# Connector_3.net
KiCad netlist of a schematic drawn in Altium Designer
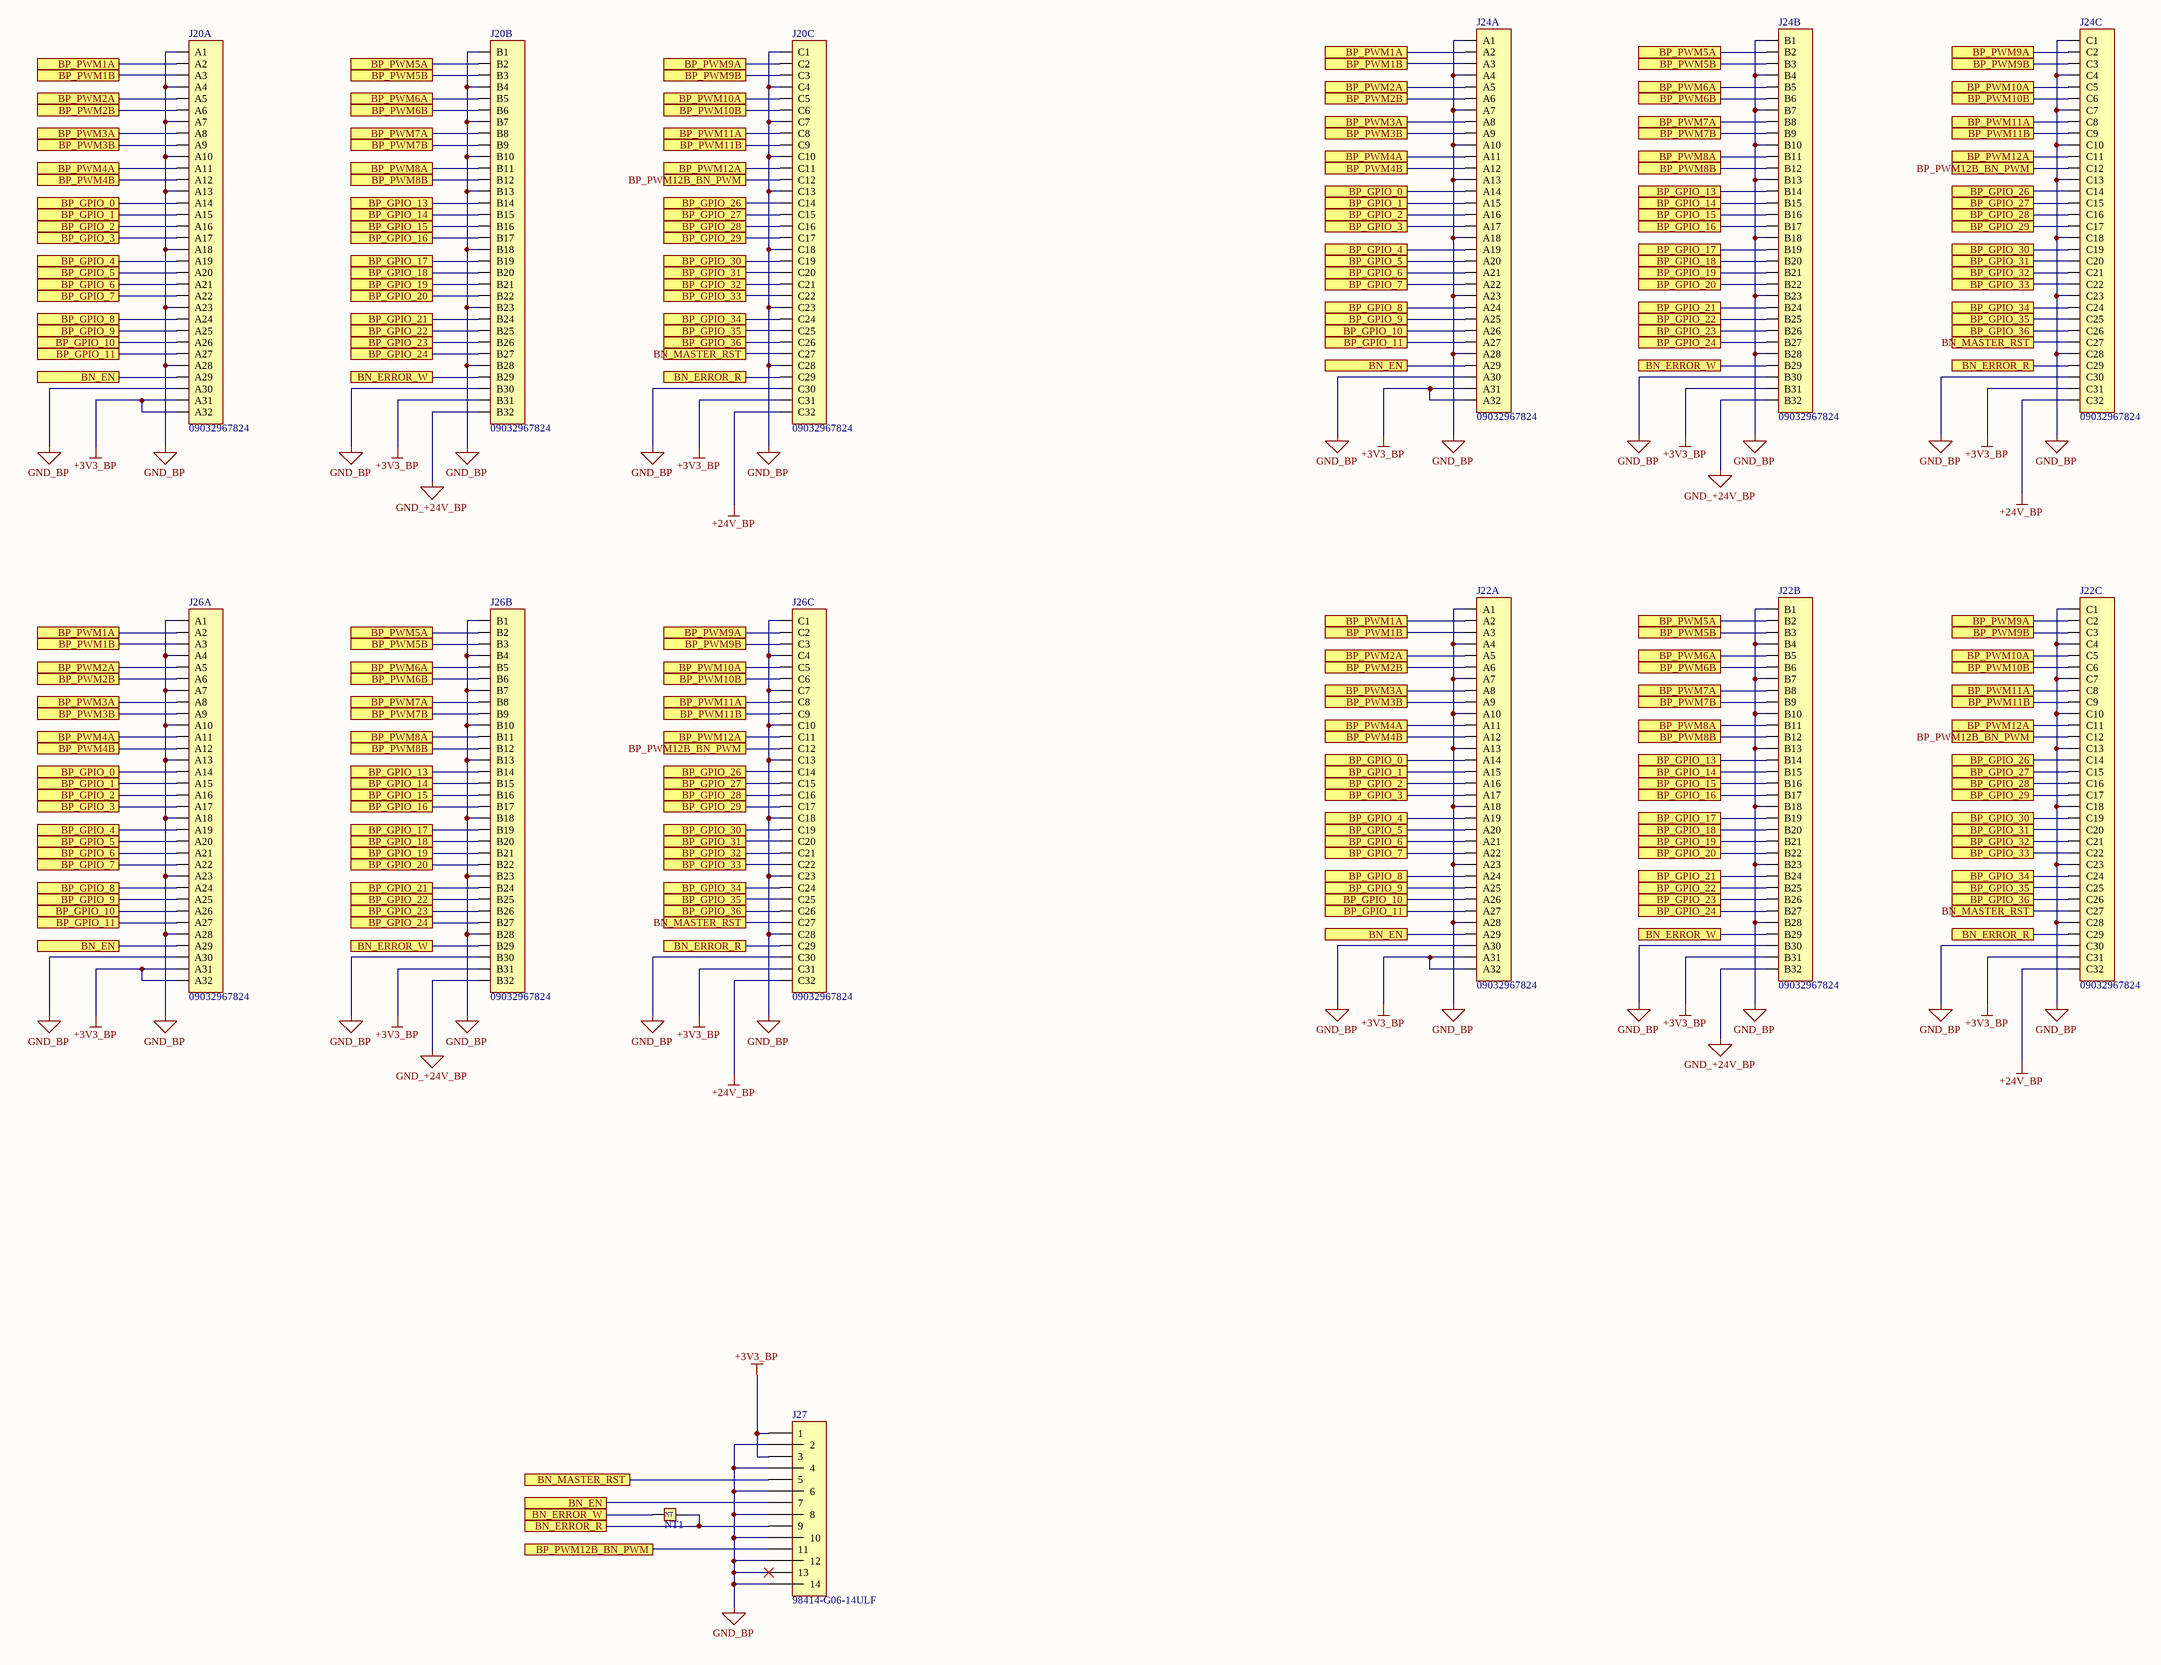
[diagram p0: Connector_3.SchDoc]

(export (version "E")
  (design (tool "Eeschema 10.0.6"))
  (components
    (comp (ref "J20")
      (value "09032967824")
      (footprint "DIN41612 FEM 3x32 ABC Straight")
      (description "DIN41612 FEM 3X32 ABC STRAIGHT")
      (fields (field (name "MANUFACTURER") "Harting"))
      (libsource (lib "Connector") (part "DIN41612 FEM 3X32 STRAIGHT"))
    )
    (comp (ref "J22")
      (value "09032967824")
      (footprint "DIN41612 FEM 3x32 ABC Straight")
      (description "DIN41612 FEM 3X32 ABC STRAIGHT")
      (fields (field (name "MANUFACTURER") "Harting"))
      (libsource (lib "Connector") (part "DIN41612 FEM 3X32 STRAIGHT"))
    )
    (comp (ref "J24")
      (value "09032967824")
      (footprint "DIN41612 FEM 3x32 ABC Straight")
      (description "DIN41612 FEM 3X32 ABC STRAIGHT")
      (fields (field (name "MANUFACTURER") "Harting"))
      (libsource (lib "Connector") (part "DIN41612 FEM 3X32 STRAIGHT"))
    )
    (comp (ref "J26")
      (value "09032967824")
      (footprint "DIN41612 FEM 3x32 ABC Straight")
      (description "DIN41612 FEM 3X32 ABC STRAIGHT")
      (fields (field (name "MANUFACTURER") "Harting"))
      (libsource (lib "Connector") (part "DIN41612 FEM 3X32 STRAIGHT"))
    )
    (comp (ref "J27")
      (value "98414-G06-14ULF")
      (footprint "FlatCable2x7 2MM Straight TH FCI 98414-G06-14ULF")
      (description "FlatCable2x7")
      (fields (field (name "MANUFACTURER") "Amphenol FCI"))
      (libsource (lib "Connector") (part "FlatCable2x7"))
    )
    (comp (ref "NT1")
      (value "Net Tie")
      (footprint "NET TIE 1005")
      (description "Connection for 2 different NETNAME")
      (libsource (lib "Jumper") (part "Net Tie"))
    )
  )
  (nets
    (net (code "1") (name "+3V3_BP") (class "Default")
      (node (ref "J20") (pin "A31") (pinfunction "A31_A31") (pintype "passive"))
      (node (ref "J20") (pin "A32") (pinfunction "A32_A32") (pintype "passive"))
      (node (ref "J20") (pin "B31") (pinfunction "B31_B31") (pintype "passive"))
      (node (ref "J20") (pin "C31") (pinfunction "C31_C31") (pintype "passive"))
      (node (ref "J22") (pin "A31") (pinfunction "A31_A31") (pintype "passive"))
      (node (ref "J22") (pin "A32") (pinfunction "A32_A32") (pintype "passive"))
      (node (ref "J22") (pin "B31") (pinfunction "B31_B31") (pintype "passive"))
      (node (ref "J22") (pin "C31") (pinfunction "C31_C31") (pintype "passive"))
      (node (ref "J24") (pin "A31") (pinfunction "A31_A31") (pintype "passive"))
      (node (ref "J24") (pin "A32") (pinfunction "A32_A32") (pintype "passive"))
      (node (ref "J24") (pin "B31") (pinfunction "B31_B31") (pintype "passive"))
      (node (ref "J24") (pin "C31") (pinfunction "C31_C31") (pintype "passive"))
      (node (ref "J26") (pin "A31") (pinfunction "A31_A31") (pintype "passive"))
      (node (ref "J26") (pin "A32") (pinfunction "A32_A32") (pintype "passive"))
      (node (ref "J26") (pin "B31") (pinfunction "B31_B31") (pintype "passive"))
      (node (ref "J26") (pin "C31") (pinfunction "C31_C31") (pintype "passive"))
      (node (ref "J27") (pin "1") (pinfunction "1_1") (pintype "passive"))
      (node (ref "J27") (pin "3") (pinfunction "3_3") (pintype "passive"))
    )
    (net (code "2") (name "+24V_BP") (class "Default")
      (node (ref "J20") (pin "C32") (pinfunction "C32_C32") (pintype "passive"))
      (node (ref "J22") (pin "C32") (pinfunction "C32_C32") (pintype "passive"))
      (node (ref "J24") (pin "C32") (pinfunction "C32_C32") (pintype "passive"))
      (node (ref "J26") (pin "C32") (pinfunction "C32_C32") (pintype "passive"))
    )
    (net (code "3") (name "/BN_EN") (class "Default")
      (node (ref "J20") (pin "A29") (pinfunction "A29_A29") (pintype "passive"))
      (node (ref "J22") (pin "A29") (pinfunction "A29_A29") (pintype "passive"))
      (node (ref "J24") (pin "A29") (pinfunction "A29_A29") (pintype "passive"))
      (node (ref "J26") (pin "A29") (pinfunction "A29_A29") (pintype "passive"))
      (node (ref "J27") (pin "7") (pinfunction "7_7") (pintype "passive"))
    )
    (net (code "4") (name "/BN_ERROR_R") (class "Default")
      (node (ref "J20") (pin "C29") (pinfunction "C29_C29") (pintype "passive"))
      (node (ref "J22") (pin "C29") (pinfunction "C29_C29") (pintype "passive"))
      (node (ref "J24") (pin "C29") (pinfunction "C29_C29") (pintype "passive"))
      (node (ref "J26") (pin "C29") (pinfunction "C29_C29") (pintype "passive"))
      (node (ref "J27") (pin "9") (pinfunction "9_9") (pintype "passive"))
      (node (ref "NT1") (pin "2") (pinfunction "2_2") (pintype "passive"))
    )
    (net (code "5") (name "/BN_ERROR_W") (class "Default")
      (node (ref "J20") (pin "B29") (pinfunction "B29_B29") (pintype "passive"))
      (node (ref "J22") (pin "B29") (pinfunction "B29_B29") (pintype "passive"))
      (node (ref "J24") (pin "B29") (pinfunction "B29_B29") (pintype "passive"))
      (node (ref "J26") (pin "B29") (pinfunction "B29_B29") (pintype "passive"))
      (node (ref "NT1") (pin "1") (pinfunction "1_1") (pintype "passive"))
    )
    (net (code "6") (name "/BN_MASTER_RST") (class "Default")
      (node (ref "J20") (pin "C27") (pinfunction "C27_C27") (pintype "passive"))
      (node (ref "J22") (pin "C27") (pinfunction "C27_C27") (pintype "passive"))
      (node (ref "J24") (pin "C27") (pinfunction "C27_C27") (pintype "passive"))
      (node (ref "J26") (pin "C27") (pinfunction "C27_C27") (pintype "passive"))
      (node (ref "J27") (pin "5") (pinfunction "5_5") (pintype "passive"))
    )
    (net (code "7") (name "/BP_GPIO_0") (class "Default")
      (node (ref "J20") (pin "A14") (pinfunction "A14_A14") (pintype "passive"))
      (node (ref "J22") (pin "A14") (pinfunction "A14_A14") (pintype "passive"))
      (node (ref "J24") (pin "A14") (pinfunction "A14_A14") (pintype "passive"))
      (node (ref "J26") (pin "A14") (pinfunction "A14_A14") (pintype "passive"))
    )
    (net (code "8") (name "/BP_GPIO_1") (class "Default")
      (node (ref "J20") (pin "A15") (pinfunction "A15_A15") (pintype "passive"))
      (node (ref "J22") (pin "A15") (pinfunction "A15_A15") (pintype "passive"))
      (node (ref "J24") (pin "A15") (pinfunction "A15_A15") (pintype "passive"))
      (node (ref "J26") (pin "A15") (pinfunction "A15_A15") (pintype "passive"))
    )
    (net (code "9") (name "/BP_GPIO_2") (class "Default")
      (node (ref "J20") (pin "A16") (pinfunction "A16_A16") (pintype "passive"))
      (node (ref "J22") (pin "A16") (pinfunction "A16_A16") (pintype "passive"))
      (node (ref "J24") (pin "A16") (pinfunction "A16_A16") (pintype "passive"))
      (node (ref "J26") (pin "A16") (pinfunction "A16_A16") (pintype "passive"))
    )
    (net (code "10") (name "/BP_GPIO_3") (class "Default")
      (node (ref "J20") (pin "A17") (pinfunction "A17_A17") (pintype "passive"))
      (node (ref "J22") (pin "A17") (pinfunction "A17_A17") (pintype "passive"))
      (node (ref "J24") (pin "A17") (pinfunction "A17_A17") (pintype "passive"))
      (node (ref "J26") (pin "A17") (pinfunction "A17_A17") (pintype "passive"))
    )
    (net (code "11") (name "/BP_GPIO_4") (class "Default")
      (node (ref "J20") (pin "A19") (pinfunction "A19_A19") (pintype "passive"))
      (node (ref "J22") (pin "A19") (pinfunction "A19_A19") (pintype "passive"))
      (node (ref "J24") (pin "A19") (pinfunction "A19_A19") (pintype "passive"))
      (node (ref "J26") (pin "A19") (pinfunction "A19_A19") (pintype "passive"))
    )
    (net (code "12") (name "/BP_GPIO_5") (class "Default")
      (node (ref "J20") (pin "A20") (pinfunction "A20_A20") (pintype "passive"))
      (node (ref "J22") (pin "A20") (pinfunction "A20_A20") (pintype "passive"))
      (node (ref "J24") (pin "A20") (pinfunction "A20_A20") (pintype "passive"))
      (node (ref "J26") (pin "A20") (pinfunction "A20_A20") (pintype "passive"))
    )
    (net (code "13") (name "/BP_GPIO_6") (class "Default")
      (node (ref "J20") (pin "A21") (pinfunction "A21_A21") (pintype "passive"))
      (node (ref "J22") (pin "A21") (pinfunction "A21_A21") (pintype "passive"))
      (node (ref "J24") (pin "A21") (pinfunction "A21_A21") (pintype "passive"))
      (node (ref "J26") (pin "A21") (pinfunction "A21_A21") (pintype "passive"))
    )
    (net (code "14") (name "/BP_GPIO_7") (class "Default")
      (node (ref "J20") (pin "A22") (pinfunction "A22_A22") (pintype "passive"))
      (node (ref "J22") (pin "A22") (pinfunction "A22_A22") (pintype "passive"))
      (node (ref "J24") (pin "A22") (pinfunction "A22_A22") (pintype "passive"))
      (node (ref "J26") (pin "A22") (pinfunction "A22_A22") (pintype "passive"))
    )
    (net (code "15") (name "/BP_GPIO_8") (class "Default")
      (node (ref "J20") (pin "A24") (pinfunction "A24_A24") (pintype "passive"))
      (node (ref "J22") (pin "A24") (pinfunction "A24_A24") (pintype "passive"))
      (node (ref "J24") (pin "A24") (pinfunction "A24_A24") (pintype "passive"))
      (node (ref "J26") (pin "A24") (pinfunction "A24_A24") (pintype "passive"))
    )
    (net (code "16") (name "/BP_GPIO_9") (class "Default")
      (node (ref "J20") (pin "A25") (pinfunction "A25_A25") (pintype "passive"))
      (node (ref "J22") (pin "A25") (pinfunction "A25_A25") (pintype "passive"))
      (node (ref "J24") (pin "A25") (pinfunction "A25_A25") (pintype "passive"))
      (node (ref "J26") (pin "A25") (pinfunction "A25_A25") (pintype "passive"))
    )
    (net (code "17") (name "/BP_GPIO_10") (class "Default")
      (node (ref "J20") (pin "A26") (pinfunction "A26_A26") (pintype "passive"))
      (node (ref "J22") (pin "A26") (pinfunction "A26_A26") (pintype "passive"))
      (node (ref "J24") (pin "A26") (pinfunction "A26_A26") (pintype "passive"))
      (node (ref "J26") (pin "A26") (pinfunction "A26_A26") (pintype "passive"))
    )
    (net (code "18") (name "/BP_GPIO_11") (class "Default")
      (node (ref "J20") (pin "A27") (pinfunction "A27_A27") (pintype "passive"))
      (node (ref "J22") (pin "A27") (pinfunction "A27_A27") (pintype "passive"))
      (node (ref "J24") (pin "A27") (pinfunction "A27_A27") (pintype "passive"))
      (node (ref "J26") (pin "A27") (pinfunction "A27_A27") (pintype "passive"))
    )
    (net (code "19") (name "/BP_GPIO_13") (class "Default")
      (node (ref "J20") (pin "B14") (pinfunction "B14_B14") (pintype "passive"))
      (node (ref "J22") (pin "B14") (pinfunction "B14_B14") (pintype "passive"))
      (node (ref "J24") (pin "B14") (pinfunction "B14_B14") (pintype "passive"))
      (node (ref "J26") (pin "B14") (pinfunction "B14_B14") (pintype "passive"))
    )
    (net (code "20") (name "/BP_GPIO_14") (class "Default")
      (node (ref "J20") (pin "B15") (pinfunction "B15_B15") (pintype "passive"))
      (node (ref "J22") (pin "B15") (pinfunction "B15_B15") (pintype "passive"))
      (node (ref "J24") (pin "B15") (pinfunction "B15_B15") (pintype "passive"))
      (node (ref "J26") (pin "B15") (pinfunction "B15_B15") (pintype "passive"))
    )
    (net (code "21") (name "/BP_GPIO_15") (class "Default")
      (node (ref "J20") (pin "B16") (pinfunction "B16_B16") (pintype "passive"))
      (node (ref "J22") (pin "B16") (pinfunction "B16_B16") (pintype "passive"))
      (node (ref "J24") (pin "B16") (pinfunction "B16_B16") (pintype "passive"))
      (node (ref "J26") (pin "B16") (pinfunction "B16_B16") (pintype "passive"))
    )
    (net (code "22") (name "/BP_GPIO_16") (class "Default")
      (node (ref "J20") (pin "B17") (pinfunction "B17_B17") (pintype "passive"))
      (node (ref "J22") (pin "B17") (pinfunction "B17_B17") (pintype "passive"))
      (node (ref "J24") (pin "B17") (pinfunction "B17_B17") (pintype "passive"))
      (node (ref "J26") (pin "B17") (pinfunction "B17_B17") (pintype "passive"))
    )
    (net (code "23") (name "/BP_GPIO_17") (class "Default")
      (node (ref "J20") (pin "B19") (pinfunction "B19_B19") (pintype "passive"))
      (node (ref "J22") (pin "B19") (pinfunction "B19_B19") (pintype "passive"))
      (node (ref "J24") (pin "B19") (pinfunction "B19_B19") (pintype "passive"))
      (node (ref "J26") (pin "B19") (pinfunction "B19_B19") (pintype "passive"))
    )
    (net (code "24") (name "/BP_GPIO_18") (class "Default")
      (node (ref "J20") (pin "B20") (pinfunction "B20_B20") (pintype "passive"))
      (node (ref "J22") (pin "B20") (pinfunction "B20_B20") (pintype "passive"))
      (node (ref "J24") (pin "B20") (pinfunction "B20_B20") (pintype "passive"))
      (node (ref "J26") (pin "B20") (pinfunction "B20_B20") (pintype "passive"))
    )
    (net (code "25") (name "/BP_GPIO_19") (class "Default")
      (node (ref "J20") (pin "B21") (pinfunction "B21_B21") (pintype "passive"))
      (node (ref "J22") (pin "B21") (pinfunction "B21_B21") (pintype "passive"))
      (node (ref "J24") (pin "B21") (pinfunction "B21_B21") (pintype "passive"))
      (node (ref "J26") (pin "B21") (pinfunction "B21_B21") (pintype "passive"))
    )
    (net (code "26") (name "/BP_GPIO_20") (class "Default")
      (node (ref "J20") (pin "B22") (pinfunction "B22_B22") (pintype "passive"))
      (node (ref "J22") (pin "B22") (pinfunction "B22_B22") (pintype "passive"))
      (node (ref "J24") (pin "B22") (pinfunction "B22_B22") (pintype "passive"))
      (node (ref "J26") (pin "B22") (pinfunction "B22_B22") (pintype "passive"))
    )
    (net (code "27") (name "/BP_GPIO_21") (class "Default")
      (node (ref "J20") (pin "B24") (pinfunction "B24_B24") (pintype "passive"))
      (node (ref "J22") (pin "B24") (pinfunction "B24_B24") (pintype "passive"))
      (node (ref "J24") (pin "B24") (pinfunction "B24_B24") (pintype "passive"))
      (node (ref "J26") (pin "B24") (pinfunction "B24_B24") (pintype "passive"))
    )
    (net (code "28") (name "/BP_GPIO_22") (class "Default")
      (node (ref "J20") (pin "B25") (pinfunction "B25_B25") (pintype "passive"))
      (node (ref "J22") (pin "B25") (pinfunction "B25_B25") (pintype "passive"))
      (node (ref "J24") (pin "B25") (pinfunction "B25_B25") (pintype "passive"))
      (node (ref "J26") (pin "B25") (pinfunction "B25_B25") (pintype "passive"))
    )
    (net (code "29") (name "/BP_GPIO_23") (class "Default")
      (node (ref "J20") (pin "B26") (pinfunction "B26_B26") (pintype "passive"))
      (node (ref "J22") (pin "B26") (pinfunction "B26_B26") (pintype "passive"))
      (node (ref "J24") (pin "B26") (pinfunction "B26_B26") (pintype "passive"))
      (node (ref "J26") (pin "B26") (pinfunction "B26_B26") (pintype "passive"))
    )
    (net (code "30") (name "/BP_GPIO_24") (class "Default")
      (node (ref "J20") (pin "B27") (pinfunction "B27_B27") (pintype "passive"))
      (node (ref "J22") (pin "B27") (pinfunction "B27_B27") (pintype "passive"))
      (node (ref "J24") (pin "B27") (pinfunction "B27_B27") (pintype "passive"))
      (node (ref "J26") (pin "B27") (pinfunction "B27_B27") (pintype "passive"))
    )
    (net (code "31") (name "/BP_GPIO_26") (class "Default")
      (node (ref "J20") (pin "C14") (pinfunction "C14_C14") (pintype "passive"))
      (node (ref "J22") (pin "C14") (pinfunction "C14_C14") (pintype "passive"))
      (node (ref "J24") (pin "C14") (pinfunction "C14_C14") (pintype "passive"))
      (node (ref "J26") (pin "C14") (pinfunction "C14_C14") (pintype "passive"))
    )
    (net (code "32") (name "/BP_GPIO_27") (class "Default")
      (node (ref "J20") (pin "C15") (pinfunction "C15_C15") (pintype "passive"))
      (node (ref "J22") (pin "C15") (pinfunction "C15_C15") (pintype "passive"))
      (node (ref "J24") (pin "C15") (pinfunction "C15_C15") (pintype "passive"))
      (node (ref "J26") (pin "C15") (pinfunction "C15_C15") (pintype "passive"))
    )
    (net (code "33") (name "/BP_GPIO_28") (class "Default")
      (node (ref "J20") (pin "C16") (pinfunction "C16_C16") (pintype "passive"))
      (node (ref "J22") (pin "C16") (pinfunction "C16_C16") (pintype "passive"))
      (node (ref "J24") (pin "C16") (pinfunction "C16_C16") (pintype "passive"))
      (node (ref "J26") (pin "C16") (pinfunction "C16_C16") (pintype "passive"))
    )
    (net (code "34") (name "/BP_GPIO_29") (class "Default")
      (node (ref "J20") (pin "C17") (pinfunction "C17_C17") (pintype "passive"))
      (node (ref "J22") (pin "C17") (pinfunction "C17_C17") (pintype "passive"))
      (node (ref "J24") (pin "C17") (pinfunction "C17_C17") (pintype "passive"))
      (node (ref "J26") (pin "C17") (pinfunction "C17_C17") (pintype "passive"))
    )
    (net (code "35") (name "/BP_GPIO_30") (class "Default")
      (node (ref "J20") (pin "C19") (pinfunction "C19_C19") (pintype "passive"))
      (node (ref "J22") (pin "C19") (pinfunction "C19_C19") (pintype "passive"))
      (node (ref "J24") (pin "C19") (pinfunction "C19_C19") (pintype "passive"))
      (node (ref "J26") (pin "C19") (pinfunction "C19_C19") (pintype "passive"))
    )
    (net (code "36") (name "/BP_GPIO_31") (class "Default")
      (node (ref "J20") (pin "C20") (pinfunction "C20_C20") (pintype "passive"))
      (node (ref "J22") (pin "C20") (pinfunction "C20_C20") (pintype "passive"))
      (node (ref "J24") (pin "C20") (pinfunction "C20_C20") (pintype "passive"))
      (node (ref "J26") (pin "C20") (pinfunction "C20_C20") (pintype "passive"))
    )
    (net (code "37") (name "/BP_GPIO_32") (class "Default")
      (node (ref "J20") (pin "C21") (pinfunction "C21_C21") (pintype "passive"))
      (node (ref "J22") (pin "C21") (pinfunction "C21_C21") (pintype "passive"))
      (node (ref "J24") (pin "C21") (pinfunction "C21_C21") (pintype "passive"))
      (node (ref "J26") (pin "C21") (pinfunction "C21_C21") (pintype "passive"))
    )
    (net (code "38") (name "/BP_GPIO_33") (class "Default")
      (node (ref "J20") (pin "C22") (pinfunction "C22_C22") (pintype "passive"))
      (node (ref "J22") (pin "C22") (pinfunction "C22_C22") (pintype "passive"))
      (node (ref "J24") (pin "C22") (pinfunction "C22_C22") (pintype "passive"))
      (node (ref "J26") (pin "C22") (pinfunction "C22_C22") (pintype "passive"))
    )
    (net (code "39") (name "/BP_GPIO_34") (class "Default")
      (node (ref "J20") (pin "C24") (pinfunction "C24_C24") (pintype "passive"))
      (node (ref "J22") (pin "C24") (pinfunction "C24_C24") (pintype "passive"))
      (node (ref "J24") (pin "C24") (pinfunction "C24_C24") (pintype "passive"))
      (node (ref "J26") (pin "C24") (pinfunction "C24_C24") (pintype "passive"))
    )
    (net (code "40") (name "/BP_GPIO_35") (class "Default")
      (node (ref "J20") (pin "C25") (pinfunction "C25_C25") (pintype "passive"))
      (node (ref "J22") (pin "C25") (pinfunction "C25_C25") (pintype "passive"))
      (node (ref "J24") (pin "C25") (pinfunction "C25_C25") (pintype "passive"))
      (node (ref "J26") (pin "C25") (pinfunction "C25_C25") (pintype "passive"))
    )
    (net (code "41") (name "/BP_GPIO_36") (class "Default")
      (node (ref "J20") (pin "C26") (pinfunction "C26_C26") (pintype "passive"))
      (node (ref "J22") (pin "C26") (pinfunction "C26_C26") (pintype "passive"))
      (node (ref "J24") (pin "C26") (pinfunction "C26_C26") (pintype "passive"))
      (node (ref "J26") (pin "C26") (pinfunction "C26_C26") (pintype "passive"))
    )
    (net (code "42") (name "/BP_PWM1A") (class "Default")
      (node (ref "J20") (pin "A2") (pinfunction "A2_A2") (pintype "passive"))
      (node (ref "J22") (pin "A2") (pinfunction "A2_A2") (pintype "passive"))
      (node (ref "J24") (pin "A2") (pinfunction "A2_A2") (pintype "passive"))
      (node (ref "J26") (pin "A2") (pinfunction "A2_A2") (pintype "passive"))
    )
    (net (code "43") (name "/BP_PWM1B") (class "Default")
      (node (ref "J20") (pin "A3") (pinfunction "A3_A3") (pintype "passive"))
      (node (ref "J22") (pin "A3") (pinfunction "A3_A3") (pintype "passive"))
      (node (ref "J24") (pin "A3") (pinfunction "A3_A3") (pintype "passive"))
      (node (ref "J26") (pin "A3") (pinfunction "A3_A3") (pintype "passive"))
    )
    (net (code "44") (name "/BP_PWM2A") (class "Default")
      (node (ref "J20") (pin "A5") (pinfunction "A5_A5") (pintype "passive"))
      (node (ref "J22") (pin "A5") (pinfunction "A5_A5") (pintype "passive"))
      (node (ref "J24") (pin "A5") (pinfunction "A5_A5") (pintype "passive"))
      (node (ref "J26") (pin "A5") (pinfunction "A5_A5") (pintype "passive"))
    )
    (net (code "45") (name "/BP_PWM2B") (class "Default")
      (node (ref "J20") (pin "A6") (pinfunction "A6_A6") (pintype "passive"))
      (node (ref "J22") (pin "A6") (pinfunction "A6_A6") (pintype "passive"))
      (node (ref "J24") (pin "A6") (pinfunction "A6_A6") (pintype "passive"))
      (node (ref "J26") (pin "A6") (pinfunction "A6_A6") (pintype "passive"))
    )
    (net (code "46") (name "/BP_PWM3A") (class "Default")
      (node (ref "J20") (pin "A8") (pinfunction "A8_A8") (pintype "passive"))
      (node (ref "J22") (pin "A8") (pinfunction "A8_A8") (pintype "passive"))
      (node (ref "J24") (pin "A8") (pinfunction "A8_A8") (pintype "passive"))
      (node (ref "J26") (pin "A8") (pinfunction "A8_A8") (pintype "passive"))
    )
    (net (code "47") (name "/BP_PWM3B") (class "Default")
      (node (ref "J20") (pin "A9") (pinfunction "A9_A9") (pintype "passive"))
      (node (ref "J22") (pin "A9") (pinfunction "A9_A9") (pintype "passive"))
      (node (ref "J24") (pin "A9") (pinfunction "A9_A9") (pintype "passive"))
      (node (ref "J26") (pin "A9") (pinfunction "A9_A9") (pintype "passive"))
    )
    (net (code "48") (name "/BP_PWM4A") (class "Default")
      (node (ref "J20") (pin "A11") (pinfunction "A11_A11") (pintype "passive"))
      (node (ref "J22") (pin "A11") (pinfunction "A11_A11") (pintype "passive"))
      (node (ref "J24") (pin "A11") (pinfunction "A11_A11") (pintype "passive"))
      (node (ref "J26") (pin "A11") (pinfunction "A11_A11") (pintype "passive"))
    )
    (net (code "49") (name "/BP_PWM4B") (class "Default")
      (node (ref "J20") (pin "A12") (pinfunction "A12_A12") (pintype "passive"))
      (node (ref "J22") (pin "A12") (pinfunction "A12_A12") (pintype "passive"))
      (node (ref "J24") (pin "A12") (pinfunction "A12_A12") (pintype "passive"))
      (node (ref "J26") (pin "A12") (pinfunction "A12_A12") (pintype "passive"))
    )
    (net (code "50") (name "/BP_PWM5A") (class "Default")
      (node (ref "J20") (pin "B2") (pinfunction "B2_B2") (pintype "passive"))
      (node (ref "J22") (pin "B2") (pinfunction "B2_B2") (pintype "passive"))
      (node (ref "J24") (pin "B2") (pinfunction "B2_B2") (pintype "passive"))
      (node (ref "J26") (pin "B2") (pinfunction "B2_B2") (pintype "passive"))
    )
    (net (code "51") (name "/BP_PWM5B") (class "Default")
      (node (ref "J20") (pin "B3") (pinfunction "B3_B3") (pintype "passive"))
      (node (ref "J22") (pin "B3") (pinfunction "B3_B3") (pintype "passive"))
      (node (ref "J24") (pin "B3") (pinfunction "B3_B3") (pintype "passive"))
      (node (ref "J26") (pin "B3") (pinfunction "B3_B3") (pintype "passive"))
    )
    (net (code "52") (name "/BP_PWM6A") (class "Default")
      (node (ref "J20") (pin "B5") (pinfunction "B5_B5") (pintype "passive"))
      (node (ref "J22") (pin "B5") (pinfunction "B5_B5") (pintype "passive"))
      (node (ref "J24") (pin "B5") (pinfunction "B5_B5") (pintype "passive"))
      (node (ref "J26") (pin "B5") (pinfunction "B5_B5") (pintype "passive"))
    )
    (net (code "53") (name "/BP_PWM6B") (class "Default")
      (node (ref "J20") (pin "B6") (pinfunction "B6_B6") (pintype "passive"))
      (node (ref "J22") (pin "B6") (pinfunction "B6_B6") (pintype "passive"))
      (node (ref "J24") (pin "B6") (pinfunction "B6_B6") (pintype "passive"))
      (node (ref "J26") (pin "B6") (pinfunction "B6_B6") (pintype "passive"))
    )
    (net (code "54") (name "/BP_PWM7A") (class "Default")
      (node (ref "J20") (pin "B8") (pinfunction "B8_B8") (pintype "passive"))
      (node (ref "J22") (pin "B8") (pinfunction "B8_B8") (pintype "passive"))
      (node (ref "J24") (pin "B8") (pinfunction "B8_B8") (pintype "passive"))
      (node (ref "J26") (pin "B8") (pinfunction "B8_B8") (pintype "passive"))
    )
    (net (code "55") (name "/BP_PWM7B") (class "Default")
      (node (ref "J20") (pin "B9") (pinfunction "B9_B9") (pintype "passive"))
      (node (ref "J22") (pin "B9") (pinfunction "B9_B9") (pintype "passive"))
      (node (ref "J24") (pin "B9") (pinfunction "B9_B9") (pintype "passive"))
      (node (ref "J26") (pin "B9") (pinfunction "B9_B9") (pintype "passive"))
    )
    (net (code "56") (name "/BP_PWM8A") (class "Default")
      (node (ref "J20") (pin "B11") (pinfunction "B11_B11") (pintype "passive"))
      (node (ref "J22") (pin "B11") (pinfunction "B11_B11") (pintype "passive"))
      (node (ref "J24") (pin "B11") (pinfunction "B11_B11") (pintype "passive"))
      (node (ref "J26") (pin "B11") (pinfunction "B11_B11") (pintype "passive"))
    )
    (net (code "57") (name "/BP_PWM8B") (class "Default")
      (node (ref "J20") (pin "B12") (pinfunction "B12_B12") (pintype "passive"))
      (node (ref "J22") (pin "B12") (pinfunction "B12_B12") (pintype "passive"))
      (node (ref "J24") (pin "B12") (pinfunction "B12_B12") (pintype "passive"))
      (node (ref "J26") (pin "B12") (pinfunction "B12_B12") (pintype "passive"))
    )
    (net (code "58") (name "/BP_PWM9A") (class "Default")
      (node (ref "J20") (pin "C2") (pinfunction "C2_C2") (pintype "passive"))
      (node (ref "J22") (pin "C2") (pinfunction "C2_C2") (pintype "passive"))
      (node (ref "J24") (pin "C2") (pinfunction "C2_C2") (pintype "passive"))
      (node (ref "J26") (pin "C2") (pinfunction "C2_C2") (pintype "passive"))
    )
    (net (code "59") (name "/BP_PWM9B") (class "Default")
      (node (ref "J20") (pin "C3") (pinfunction "C3_C3") (pintype "passive"))
      (node (ref "J22") (pin "C3") (pinfunction "C3_C3") (pintype "passive"))
      (node (ref "J24") (pin "C3") (pinfunction "C3_C3") (pintype "passive"))
      (node (ref "J26") (pin "C3") (pinfunction "C3_C3") (pintype "passive"))
    )
    (net (code "60") (name "/BP_PWM10A") (class "Default")
      (node (ref "J20") (pin "C5") (pinfunction "C5_C5") (pintype "passive"))
      (node (ref "J22") (pin "C5") (pinfunction "C5_C5") (pintype "passive"))
      (node (ref "J24") (pin "C5") (pinfunction "C5_C5") (pintype "passive"))
      (node (ref "J26") (pin "C5") (pinfunction "C5_C5") (pintype "passive"))
    )
    (net (code "61") (name "/BP_PWM10B") (class "Default")
      (node (ref "J20") (pin "C6") (pinfunction "C6_C6") (pintype "passive"))
      (node (ref "J22") (pin "C6") (pinfunction "C6_C6") (pintype "passive"))
      (node (ref "J24") (pin "C6") (pinfunction "C6_C6") (pintype "passive"))
      (node (ref "J26") (pin "C6") (pinfunction "C6_C6") (pintype "passive"))
    )
    (net (code "62") (name "/BP_PWM11A") (class "Default")
      (node (ref "J20") (pin "C8") (pinfunction "C8_C8") (pintype "passive"))
      (node (ref "J22") (pin "C8") (pinfunction "C8_C8") (pintype "passive"))
      (node (ref "J24") (pin "C8") (pinfunction "C8_C8") (pintype "passive"))
      (node (ref "J26") (pin "C8") (pinfunction "C8_C8") (pintype "passive"))
    )
    (net (code "63") (name "/BP_PWM11B") (class "Default")
      (node (ref "J20") (pin "C9") (pinfunction "C9_C9") (pintype "passive"))
      (node (ref "J22") (pin "C9") (pinfunction "C9_C9") (pintype "passive"))
      (node (ref "J24") (pin "C9") (pinfunction "C9_C9") (pintype "passive"))
      (node (ref "J26") (pin "C9") (pinfunction "C9_C9") (pintype "passive"))
    )
    (net (code "64") (name "/BP_PWM12A") (class "Default")
      (node (ref "J20") (pin "C11") (pinfunction "C11_C11") (pintype "passive"))
      (node (ref "J22") (pin "C11") (pinfunction "C11_C11") (pintype "passive"))
      (node (ref "J24") (pin "C11") (pinfunction "C11_C11") (pintype "passive"))
      (node (ref "J26") (pin "C11") (pinfunction "C11_C11") (pintype "passive"))
    )
    (net (code "65") (name "/BP_PWM12B_BN_PWM") (class "Default")
      (node (ref "J20") (pin "C12") (pinfunction "C12_C12") (pintype "passive"))
      (node (ref "J22") (pin "C12") (pinfunction "C12_C12") (pintype "passive"))
      (node (ref "J24") (pin "C12") (pinfunction "C12_C12") (pintype "passive"))
      (node (ref "J26") (pin "C12") (pinfunction "C12_C12") (pintype "passive"))
      (node (ref "J27") (pin "11") (pinfunction "11_11") (pintype "passive"))
    )
    (net (code "66") (name "GND_+24V_BP") (class "Default")
      (node (ref "J20") (pin "B32") (pinfunction "B32_B32") (pintype "passive"))
      (node (ref "J22") (pin "B32") (pinfunction "B32_B32") (pintype "passive"))
      (node (ref "J24") (pin "B32") (pinfunction "B32_B32") (pintype "passive"))
      (node (ref "J26") (pin "B32") (pinfunction "B32_B32") (pintype "passive"))
    )
    (net (code "67") (name "GND_BP") (class "Default")
      (node (ref "J20") (pin "A1") (pinfunction "A1_A1") (pintype "passive"))
      (node (ref "J20") (pin "A10") (pinfunction "A10_A10") (pintype "passive"))
      (node (ref "J20") (pin "A13") (pinfunction "A13_A13") (pintype "passive"))
      (node (ref "J20") (pin "A18") (pinfunction "A18_A18") (pintype "passive"))
      (node (ref "J20") (pin "A23") (pinfunction "A23_A23") (pintype "passive"))
      (node (ref "J20") (pin "A28") (pinfunction "A28_A28") (pintype "passive"))
      (node (ref "J20") (pin "A30") (pinfunction "A30_A30") (pintype "passive"))
      (node (ref "J20") (pin "A4") (pinfunction "A4_A4") (pintype "passive"))
      (node (ref "J20") (pin "A7") (pinfunction "A7_A7") (pintype "passive"))
      (node (ref "J20") (pin "B1") (pinfunction "B1_B1") (pintype "passive"))
      (node (ref "J20") (pin "B10") (pinfunction "B10_B10") (pintype "passive"))
      (node (ref "J20") (pin "B13") (pinfunction "B13_B13") (pintype "passive"))
      (node (ref "J20") (pin "B18") (pinfunction "B18_B18") (pintype "passive"))
      (node (ref "J20") (pin "B23") (pinfunction "B23_B23") (pintype "passive"))
      (node (ref "J20") (pin "B28") (pinfunction "B28_B28") (pintype "passive"))
      (node (ref "J20") (pin "B30") (pinfunction "B30_B30") (pintype "passive"))
      (node (ref "J20") (pin "B4") (pinfunction "B4_B4") (pintype "passive"))
      (node (ref "J20") (pin "B7") (pinfunction "B7_B7") (pintype "passive"))
      (node (ref "J20") (pin "C1") (pinfunction "C1_C1") (pintype "passive"))
      (node (ref "J20") (pin "C10") (pinfunction "C10_C10") (pintype "passive"))
      (node (ref "J20") (pin "C13") (pinfunction "C13_C13") (pintype "passive"))
      (node (ref "J20") (pin "C18") (pinfunction "C18_C18") (pintype "passive"))
      (node (ref "J20") (pin "C23") (pinfunction "C23_C23") (pintype "passive"))
      (node (ref "J20") (pin "C28") (pinfunction "C28_C28") (pintype "passive"))
      (node (ref "J20") (pin "C30") (pinfunction "C30_C30") (pintype "passive"))
      (node (ref "J20") (pin "C4") (pinfunction "C4_C4") (pintype "passive"))
      (node (ref "J20") (pin "C7") (pinfunction "C7_C7") (pintype "passive"))
      (node (ref "J22") (pin "A1") (pinfunction "A1_A1") (pintype "passive"))
      (node (ref "J22") (pin "A10") (pinfunction "A10_A10") (pintype "passive"))
      (node (ref "J22") (pin "A13") (pinfunction "A13_A13") (pintype "passive"))
      (node (ref "J22") (pin "A18") (pinfunction "A18_A18") (pintype "passive"))
      (node (ref "J22") (pin "A23") (pinfunction "A23_A23") (pintype "passive"))
      (node (ref "J22") (pin "A28") (pinfunction "A28_A28") (pintype "passive"))
      (node (ref "J22") (pin "A30") (pinfunction "A30_A30") (pintype "passive"))
      (node (ref "J22") (pin "A4") (pinfunction "A4_A4") (pintype "passive"))
      (node (ref "J22") (pin "A7") (pinfunction "A7_A7") (pintype "passive"))
      (node (ref "J22") (pin "B1") (pinfunction "B1_B1") (pintype "passive"))
      (node (ref "J22") (pin "B10") (pinfunction "B10_B10") (pintype "passive"))
      (node (ref "J22") (pin "B13") (pinfunction "B13_B13") (pintype "passive"))
      (node (ref "J22") (pin "B18") (pinfunction "B18_B18") (pintype "passive"))
      (node (ref "J22") (pin "B23") (pinfunction "B23_B23") (pintype "passive"))
      (node (ref "J22") (pin "B28") (pinfunction "B28_B28") (pintype "passive"))
      (node (ref "J22") (pin "B30") (pinfunction "B30_B30") (pintype "passive"))
      (node (ref "J22") (pin "B4") (pinfunction "B4_B4") (pintype "passive"))
      (node (ref "J22") (pin "B7") (pinfunction "B7_B7") (pintype "passive"))
      (node (ref "J22") (pin "C1") (pinfunction "C1_C1") (pintype "passive"))
      (node (ref "J22") (pin "C10") (pinfunction "C10_C10") (pintype "passive"))
      (node (ref "J22") (pin "C13") (pinfunction "C13_C13") (pintype "passive"))
      (node (ref "J22") (pin "C18") (pinfunction "C18_C18") (pintype "passive"))
      (node (ref "J22") (pin "C23") (pinfunction "C23_C23") (pintype "passive"))
      (node (ref "J22") (pin "C28") (pinfunction "C28_C28") (pintype "passive"))
      (node (ref "J22") (pin "C30") (pinfunction "C30_C30") (pintype "passive"))
      (node (ref "J22") (pin "C4") (pinfunction "C4_C4") (pintype "passive"))
      (node (ref "J22") (pin "C7") (pinfunction "C7_C7") (pintype "passive"))
      (node (ref "J24") (pin "A1") (pinfunction "A1_A1") (pintype "passive"))
      (node (ref "J24") (pin "A10") (pinfunction "A10_A10") (pintype "passive"))
      (node (ref "J24") (pin "A13") (pinfunction "A13_A13") (pintype "passive"))
      (node (ref "J24") (pin "A18") (pinfunction "A18_A18") (pintype "passive"))
      (node (ref "J24") (pin "A23") (pinfunction "A23_A23") (pintype "passive"))
      (node (ref "J24") (pin "A28") (pinfunction "A28_A28") (pintype "passive"))
      (node (ref "J24") (pin "A30") (pinfunction "A30_A30") (pintype "passive"))
      (node (ref "J24") (pin "A4") (pinfunction "A4_A4") (pintype "passive"))
      (node (ref "J24") (pin "A7") (pinfunction "A7_A7") (pintype "passive"))
      (node (ref "J24") (pin "B1") (pinfunction "B1_B1") (pintype "passive"))
      (node (ref "J24") (pin "B10") (pinfunction "B10_B10") (pintype "passive"))
      (node (ref "J24") (pin "B13") (pinfunction "B13_B13") (pintype "passive"))
      (node (ref "J24") (pin "B18") (pinfunction "B18_B18") (pintype "passive"))
      (node (ref "J24") (pin "B23") (pinfunction "B23_B23") (pintype "passive"))
      (node (ref "J24") (pin "B28") (pinfunction "B28_B28") (pintype "passive"))
      (node (ref "J24") (pin "B30") (pinfunction "B30_B30") (pintype "passive"))
      (node (ref "J24") (pin "B4") (pinfunction "B4_B4") (pintype "passive"))
      (node (ref "J24") (pin "B7") (pinfunction "B7_B7") (pintype "passive"))
      (node (ref "J24") (pin "C1") (pinfunction "C1_C1") (pintype "passive"))
      (node (ref "J24") (pin "C10") (pinfunction "C10_C10") (pintype "passive"))
      (node (ref "J24") (pin "C13") (pinfunction "C13_C13") (pintype "passive"))
      (node (ref "J24") (pin "C18") (pinfunction "C18_C18") (pintype "passive"))
      (node (ref "J24") (pin "C23") (pinfunction "C23_C23") (pintype "passive"))
      (node (ref "J24") (pin "C28") (pinfunction "C28_C28") (pintype "passive"))
      (node (ref "J24") (pin "C30") (pinfunction "C30_C30") (pintype "passive"))
      (node (ref "J24") (pin "C4") (pinfunction "C4_C4") (pintype "passive"))
      (node (ref "J24") (pin "C7") (pinfunction "C7_C7") (pintype "passive"))
      (node (ref "J26") (pin "A1") (pinfunction "A1_A1") (pintype "passive"))
      (node (ref "J26") (pin "A10") (pinfunction "A10_A10") (pintype "passive"))
      (node (ref "J26") (pin "A13") (pinfunction "A13_A13") (pintype "passive"))
      (node (ref "J26") (pin "A18") (pinfunction "A18_A18") (pintype "passive"))
      (node (ref "J26") (pin "A23") (pinfunction "A23_A23") (pintype "passive"))
      (node (ref "J26") (pin "A28") (pinfunction "A28_A28") (pintype "passive"))
      (node (ref "J26") (pin "A30") (pinfunction "A30_A30") (pintype "passive"))
      (node (ref "J26") (pin "A4") (pinfunction "A4_A4") (pintype "passive"))
      (node (ref "J26") (pin "A7") (pinfunction "A7_A7") (pintype "passive"))
      (node (ref "J26") (pin "B1") (pinfunction "B1_B1") (pintype "passive"))
      (node (ref "J26") (pin "B10") (pinfunction "B10_B10") (pintype "passive"))
      (node (ref "J26") (pin "B13") (pinfunction "B13_B13") (pintype "passive"))
      (node (ref "J26") (pin "B18") (pinfunction "B18_B18") (pintype "passive"))
      (node (ref "J26") (pin "B23") (pinfunction "B23_B23") (pintype "passive"))
      (node (ref "J26") (pin "B28") (pinfunction "B28_B28") (pintype "passive"))
      (node (ref "J26") (pin "B30") (pinfunction "B30_B30") (pintype "passive"))
      (node (ref "J26") (pin "B4") (pinfunction "B4_B4") (pintype "passive"))
      (node (ref "J26") (pin "B7") (pinfunction "B7_B7") (pintype "passive"))
      (node (ref "J26") (pin "C1") (pinfunction "C1_C1") (pintype "passive"))
      (node (ref "J26") (pin "C10") (pinfunction "C10_C10") (pintype "passive"))
      (node (ref "J26") (pin "C13") (pinfunction "C13_C13") (pintype "passive"))
      (node (ref "J26") (pin "C18") (pinfunction "C18_C18") (pintype "passive"))
      (node (ref "J26") (pin "C23") (pinfunction "C23_C23") (pintype "passive"))
      (node (ref "J26") (pin "C28") (pinfunction "C28_C28") (pintype "passive"))
      (node (ref "J26") (pin "C30") (pinfunction "C30_C30") (pintype "passive"))
      (node (ref "J26") (pin "C4") (pinfunction "C4_C4") (pintype "passive"))
      (node (ref "J26") (pin "C7") (pinfunction "C7_C7") (pintype "passive"))
      (node (ref "J27") (pin "10") (pinfunction "10_10") (pintype "passive"))
      (node (ref "J27") (pin "12") (pinfunction "12_12") (pintype "passive"))
      (node (ref "J27") (pin "13") (pinfunction "13_13") (pintype "passive"))
      (node (ref "J27") (pin "14") (pinfunction "14_14") (pintype "passive"))
      (node (ref "J27") (pin "2") (pinfunction "2_2") (pintype "passive"))
      (node (ref "J27") (pin "4") (pinfunction "4_4") (pintype "passive"))
      (node (ref "J27") (pin "6") (pinfunction "6_6") (pintype "passive"))
      (node (ref "J27") (pin "8") (pinfunction "8_8") (pintype "passive"))
    )
  )
)
